# lednode.net
KiCad netlist of a schematic drawn in EAGLE
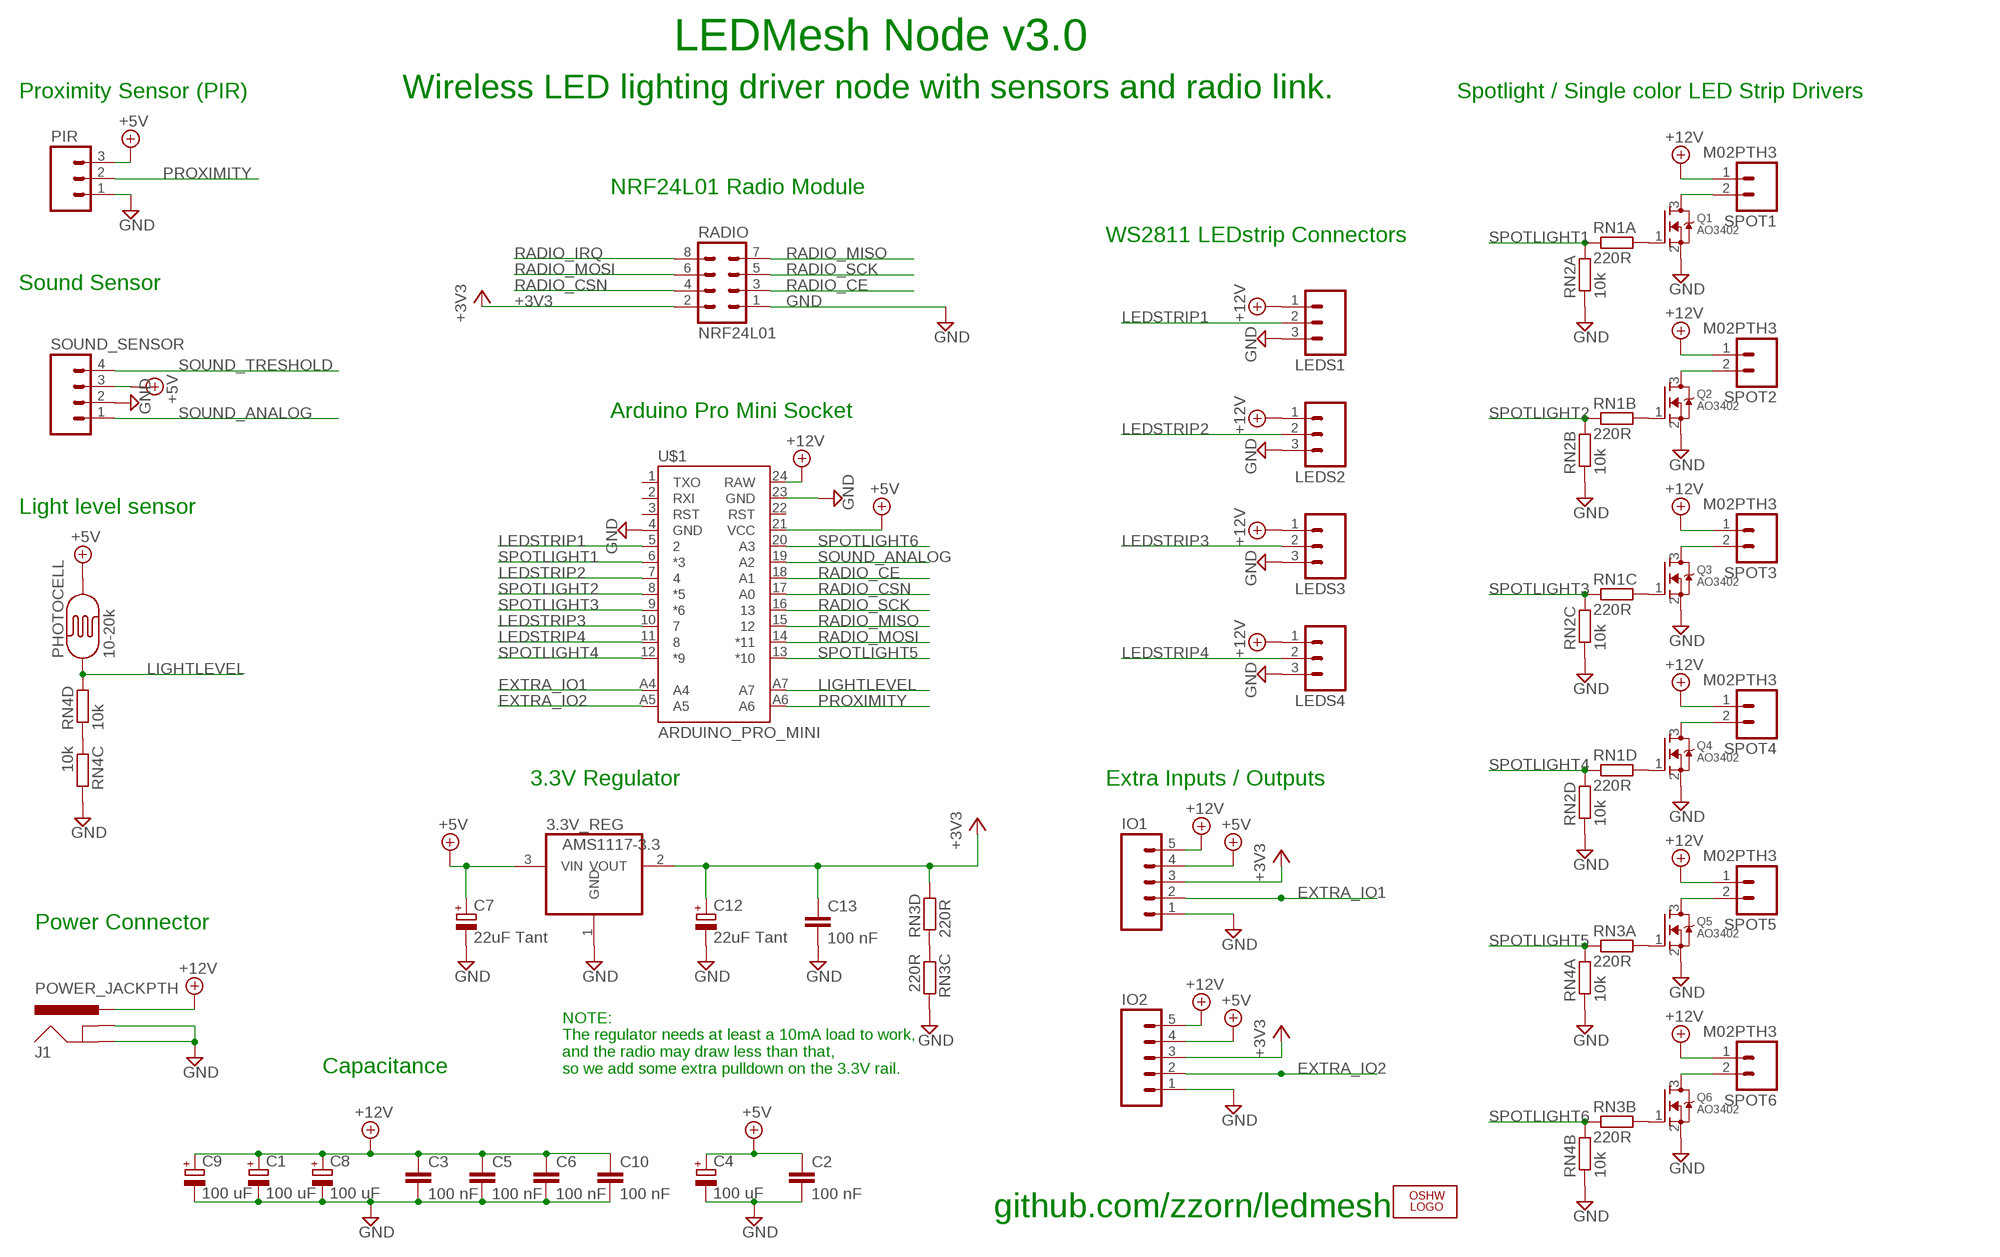
[diagram p0: schematic, sheet 1]

(export (version "E")
  (design (tool "Eeschema 10.0.6"))
  (components
    (comp (ref "3.3V_REG")
      (value "AMS1117-3.3")
      (footprint "eagle-import:SOT223")
      (fields (field (name "MPN") "REG1117"))
      (libsource (lib "eagle-import") (part "REG1117"))
    )
    (comp (ref "C1")
      (value "100 uF")
      (footprint "eagle-import:E2,5-6")
      (libsource (lib "eagle-import") (part "CPOL-EUE2.5-6"))
    )
    (comp (ref "C2")
      (value "100 nF")
      (footprint "eagle-import:C0805")
      (libsource (lib "eagle-import") (part "C-EUC0805"))
    )
    (comp (ref "C3")
      (value "100 nF")
      (footprint "eagle-import:C0805")
      (libsource (lib "eagle-import") (part "C-EUC0805"))
    )
    (comp (ref "C4")
      (value "100 uF")
      (footprint "eagle-import:E2,5-6")
      (libsource (lib "eagle-import") (part "CPOL-EUE2.5-6"))
    )
    (comp (ref "C5")
      (value "100 nF")
      (footprint "eagle-import:C0805")
      (libsource (lib "eagle-import") (part "C-EUC0805"))
    )
    (comp (ref "C6")
      (value "100 nF")
      (footprint "eagle-import:C0805")
      (libsource (lib "eagle-import") (part "C-EUC0805"))
    )
    (comp (ref "C7")
      (value "22uF Tant")
      (footprint "eagle-import:SMC_A")
      (libsource (lib "eagle-import") (part "CPOL-EUSMCA"))
    )
    (comp (ref "C8")
      (value "100 uF")
      (footprint "eagle-import:E2,5-6")
      (libsource (lib "eagle-import") (part "CPOL-EUE2.5-6"))
    )
    (comp (ref "C9")
      (value "100 uF")
      (footprint "eagle-import:E2,5-6")
      (libsource (lib "eagle-import") (part "CPOL-EUE2.5-6"))
    )
    (comp (ref "C10")
      (value "100 nF")
      (footprint "eagle-import:C0805")
      (libsource (lib "eagle-import") (part "C-EUC0805"))
    )
    (comp (ref "C12")
      (value "22uF Tant")
      (footprint "eagle-import:SMC_A")
      (libsource (lib "eagle-import") (part "CPOL-EUSMCA"))
    )
    (comp (ref "C13")
      (value "100 nF")
      (footprint "eagle-import:C0805")
      (libsource (lib "eagle-import") (part "C-EUC0805"))
    )
    (comp (ref "IO1")
      (value "M05PTH")
      (footprint "eagle-import:1X05")
      (libsource (lib "eagle-import") (part "M05PTH"))
    )
    (comp (ref "IO2")
      (value "M05PTH")
      (footprint "eagle-import:1X05")
      (libsource (lib "eagle-import") (part "M05PTH"))
    )
    (comp (ref "J1")
      (value "POWER_JACKPTH")
      (footprint "eagle-import:POWER_JACK_PTH")
      (libsource (lib "eagle-import") (part "POWER_JACKPTH"))
    )
    (comp (ref "LEDS1")
      (value "M03LONGPADS")
      (footprint "eagle-import:1X03_LONGPADS")
      (libsource (lib "eagle-import") (part "M03LONGPADS"))
    )
    (comp (ref "LEDS2")
      (value "M03LONGPADS")
      (footprint "eagle-import:1X03_LONGPADS")
      (libsource (lib "eagle-import") (part "M03LONGPADS"))
    )
    (comp (ref "LEDS3")
      (value "M03LONGPADS")
      (footprint "eagle-import:1X03_LONGPADS")
      (libsource (lib "eagle-import") (part "M03LONGPADS"))
    )
    (comp (ref "LEDS4")
      (value "M03LONGPADS")
      (footprint "eagle-import:1X03_LONGPADS")
      (libsource (lib "eagle-import") (part "M03LONGPADS"))
    )
    (comp (ref "LOGO3")
      (value "LOGO-OSHW-8MILX0100-NT")
      (footprint "eagle-import:OSHW_8X100_NOTEXT")
      (libsource (lib "eagle-import") (part "LOGO-OSHW-8MILX0100-NT"))
    )
    (comp (ref "PHOTOCELL")
      (value "10-20k")
      (footprint "eagle-import:PHOTOCELL")
      (libsource (lib "eagle-import") (part "PHOTOCELLPTH"))
    )
    (comp (ref "PIR")
      (value "M03PTH")
      (footprint "eagle-import:1X03")
      (libsource (lib "eagle-import") (part "M03PTH"))
    )
    (comp (ref "Q1")
      (value "AO3402")
      (footprint "eagle-import:SOT23-W")
      (libsource (lib "eagle-import") (part "MOSFET-NWAVE"))
    )
    (comp (ref "Q2")
      (value "AO3402")
      (footprint "eagle-import:SOT23-W")
      (libsource (lib "eagle-import") (part "MOSFET-NWAVE"))
    )
    (comp (ref "Q3")
      (value "AO3402")
      (footprint "eagle-import:SOT23-W")
      (libsource (lib "eagle-import") (part "MOSFET-NWAVE"))
    )
    (comp (ref "Q4")
      (value "AO3402")
      (footprint "eagle-import:SOT23-W")
      (libsource (lib "eagle-import") (part "MOSFET-NWAVE"))
    )
    (comp (ref "Q5")
      (value "AO3402")
      (footprint "eagle-import:SOT23-W")
      (libsource (lib "eagle-import") (part "MOSFET-NWAVE"))
    )
    (comp (ref "Q6")
      (value "AO3402")
      (footprint "eagle-import:SOT23-W")
      (libsource (lib "eagle-import") (part "MOSFET-NWAVE"))
    )
    (comp (ref "RADIO")
      (value "NRF24L01")
      (footprint "eagle-import:MA04-2")
      (libsource (lib "eagle-import") (part "MA04-2"))
    )
    (comp (ref "RN1")
      (value "220R")
      (footprint "eagle-import:RN8P-4R-CRA06S")
      (libsource (lib "eagle-import") (part "RESISTOR_ARRAY_4"))
    )
    (comp (ref "RN2")
      (value "10k")
      (footprint "eagle-import:RN8P-4R-CRA06S")
      (libsource (lib "eagle-import") (part "RESISTOR_ARRAY_4"))
    )
    (comp (ref "RN3")
      (value "220R")
      (footprint "eagle-import:RN8P-4R-CRA06S")
      (libsource (lib "eagle-import") (part "RESISTOR_ARRAY_4"))
    )
    (comp (ref "RN4")
      (value "10k")
      (footprint "eagle-import:RN8P-4R-CRA06S")
      (libsource (lib "eagle-import") (part "RESISTOR_ARRAY_4"))
    )
    (comp (ref "SOUND_SENSOR")
      (value "M041X04_NO_SILK")
      (footprint "eagle-import:1X04_NO_SILK")
      (libsource (lib "eagle-import") (part "M041X04_NO_SILK"))
    )
    (comp (ref "SPOT1")
      (value "M02PTH3")
      (footprint "eagle-import:1X02_LONGPADS")
      (libsource (lib "eagle-import") (part "M02PTH3"))
    )
    (comp (ref "SPOT2")
      (value "M02PTH3")
      (footprint "eagle-import:1X02_LONGPADS")
      (libsource (lib "eagle-import") (part "M02PTH3"))
    )
    (comp (ref "SPOT3")
      (value "M02PTH3")
      (footprint "eagle-import:1X02_LONGPADS")
      (libsource (lib "eagle-import") (part "M02PTH3"))
    )
    (comp (ref "SPOT4")
      (value "M02PTH3")
      (footprint "eagle-import:1X02_LONGPADS")
      (libsource (lib "eagle-import") (part "M02PTH3"))
    )
    (comp (ref "SPOT5")
      (value "M02PTH3")
      (footprint "eagle-import:1X02_LONGPADS")
      (libsource (lib "eagle-import") (part "M02PTH3"))
    )
    (comp (ref "SPOT6")
      (value "M02PTH3")
      (footprint "eagle-import:1X02_LONGPADS")
      (libsource (lib "eagle-import") (part "M02PTH3"))
    )
    (comp (ref "U$1")
      (value "ARDUINO_PRO_MINI")
      (footprint "eagle-import:ARDUINO_PRO_MINI")
      (libsource (lib "eagle-import") (part "ARDUINO_PRO_MINI"))
    )
  )
  (nets
    (net (code "1") (name "+3V3") (class "Default")
      (node (ref "3.3V_REG") (pin "2") (pinfunction "VOUT_2") (pintype "output"))
      (node (ref "C12") (pin "+") (pinfunction "+_+") (pintype "passive"))
      (node (ref "C13") (pin "1") (pinfunction "1_1") (pintype "passive"))
      (node (ref "IO1") (pin "3") (pinfunction "3_3") (pintype "passive"))
      (node (ref "IO2") (pin "3") (pinfunction "3_3") (pintype "passive"))
      (node (ref "RADIO") (pin "2") (pinfunction "2_2") (pintype "passive"))
      (node (ref "RN3") (pin "5") (pinfunction "2_5") (pintype "passive"))
    )
    (net (code "2") (name "+5V") (class "Default")
      (node (ref "3.3V_REG") (pin "3") (pinfunction "VIN_3") (pintype "input"))
      (node (ref "C2") (pin "1") (pinfunction "1_1") (pintype "passive"))
      (node (ref "C4") (pin "+") (pinfunction "+_+") (pintype "passive"))
      (node (ref "C7") (pin "+") (pinfunction "+_+") (pintype "passive"))
      (node (ref "IO1") (pin "4") (pinfunction "4_4") (pintype "passive"))
      (node (ref "IO2") (pin "4") (pinfunction "4_4") (pintype "passive"))
      (node (ref "PHOTOCELL") (pin "2") (pinfunction "P$2_2") (pintype "bidirectional"))
      (node (ref "PIR") (pin "3") (pinfunction "3_3") (pintype "passive"))
      (node (ref "SOUND_SENSOR") (pin "3") (pinfunction "3_3") (pintype "passive"))
      (node (ref "U$1") (pin "21") (pinfunction "VCC_21") (pintype "bidirectional"))
    )
    (net (code "3") (name "+12V") (class "Default")
      (node (ref "C1") (pin "+") (pinfunction "+_+") (pintype "passive"))
      (node (ref "C10") (pin "1") (pinfunction "1_1") (pintype "passive"))
      (node (ref "C3") (pin "1") (pinfunction "1_1") (pintype "passive"))
      (node (ref "C5") (pin "1") (pinfunction "1_1") (pintype "passive"))
      (node (ref "C6") (pin "1") (pinfunction "1_1") (pintype "passive"))
      (node (ref "C8") (pin "+") (pinfunction "+_+") (pintype "passive"))
      (node (ref "C9") (pin "+") (pinfunction "+_+") (pintype "passive"))
      (node (ref "IO1") (pin "5") (pinfunction "5_5") (pintype "passive"))
      (node (ref "IO2") (pin "5") (pinfunction "5_5") (pintype "passive"))
      (node (ref "J1") (pin "PWR") (pinfunction "PWR_PWR") (pintype "bidirectional"))
      (node (ref "LEDS1") (pin "1") (pinfunction "1_1") (pintype "passive"))
      (node (ref "LEDS2") (pin "1") (pinfunction "1_1") (pintype "passive"))
      (node (ref "LEDS3") (pin "1") (pinfunction "1_1") (pintype "passive"))
      (node (ref "LEDS4") (pin "1") (pinfunction "1_1") (pintype "passive"))
      (node (ref "SPOT1") (pin "1") (pinfunction "1_1") (pintype "passive"))
      (node (ref "SPOT2") (pin "1") (pinfunction "1_1") (pintype "passive"))
      (node (ref "SPOT3") (pin "1") (pinfunction "1_1") (pintype "passive"))
      (node (ref "SPOT4") (pin "1") (pinfunction "1_1") (pintype "passive"))
      (node (ref "SPOT5") (pin "1") (pinfunction "1_1") (pintype "passive"))
      (node (ref "SPOT6") (pin "1") (pinfunction "1_1") (pintype "passive"))
      (node (ref "U$1") (pin "24") (pinfunction "RAW_24") (pintype "bidirectional"))
    )
    (net (code "4") (name "/EXTRA_IO1") (class "Default")
      (node (ref "IO1") (pin "2") (pinfunction "2_2") (pintype "passive"))
      (node (ref "U$1") (pin "A4") (pinfunction "A4_A4") (pintype "bidirectional"))
    )
    (net (code "5") (name "/EXTRA_IO2") (class "Default")
      (node (ref "IO2") (pin "2") (pinfunction "2_2") (pintype "passive"))
      (node (ref "U$1") (pin "A5") (pinfunction "A5_A5") (pintype "bidirectional"))
    )
    (net (code "6") (name "/LEDSTRIP1") (class "Default")
      (node (ref "LEDS1") (pin "2") (pinfunction "2_2") (pintype "passive"))
      (node (ref "U$1") (pin "5") (pinfunction "2_5") (pintype "bidirectional"))
    )
    (net (code "7") (name "/LEDSTRIP2") (class "Default")
      (node (ref "LEDS2") (pin "2") (pinfunction "2_2") (pintype "passive"))
      (node (ref "U$1") (pin "7") (pinfunction "4_7") (pintype "bidirectional"))
    )
    (net (code "8") (name "/LEDSTRIP3") (class "Default")
      (node (ref "LEDS3") (pin "2") (pinfunction "2_2") (pintype "passive"))
      (node (ref "U$1") (pin "10") (pinfunction "7_10") (pintype "bidirectional"))
    )
    (net (code "9") (name "/LEDSTRIP4") (class "Default")
      (node (ref "LEDS4") (pin "2") (pinfunction "2_2") (pintype "passive"))
      (node (ref "U$1") (pin "11") (pinfunction "8_11") (pintype "bidirectional"))
    )
    (net (code "10") (name "/LIGHTLEVEL") (class "Default")
      (node (ref "PHOTOCELL") (pin "1") (pinfunction "P$1_1") (pintype "bidirectional"))
      (node (ref "RN4") (pin "5") (pinfunction "2_5") (pintype "passive"))
      (node (ref "U$1") (pin "A7") (pinfunction "A7_A7") (pintype "bidirectional"))
    )
    (net (code "11") (name "/PROXIMITY") (class "Default")
      (node (ref "PIR") (pin "2") (pinfunction "2_2") (pintype "passive"))
      (node (ref "U$1") (pin "A6") (pinfunction "A6_A6") (pintype "bidirectional"))
    )
    (net (code "12") (name "/RADIO_CE") (class "Default")
      (node (ref "RADIO") (pin "3") (pinfunction "3_3") (pintype "passive"))
      (node (ref "U$1") (pin "18") (pinfunction "A1_18") (pintype "bidirectional"))
    )
    (net (code "13") (name "/RADIO_CSN") (class "Default")
      (node (ref "RADIO") (pin "4") (pinfunction "4_4") (pintype "passive"))
      (node (ref "U$1") (pin "17") (pinfunction "A0_17") (pintype "bidirectional"))
    )
    (net (code "14") (name "/RADIO_IRQ") (class "Default")
      (node (ref "RADIO") (pin "8") (pinfunction "8_8") (pintype "passive"))
    )
    (net (code "15") (name "/RADIO_MISO") (class "Default")
      (node (ref "RADIO") (pin "7") (pinfunction "7_7") (pintype "passive"))
      (node (ref "U$1") (pin "15") (pinfunction "12_15") (pintype "bidirectional"))
    )
    (net (code "16") (name "/RADIO_MOSI") (class "Default")
      (node (ref "RADIO") (pin "6") (pinfunction "6_6") (pintype "passive"))
      (node (ref "U$1") (pin "14") (pinfunction "*11_14") (pintype "bidirectional"))
    )
    (net (code "17") (name "/RADIO_SCK") (class "Default")
      (node (ref "RADIO") (pin "5") (pinfunction "5_5") (pintype "passive"))
      (node (ref "U$1") (pin "16") (pinfunction "13_16") (pintype "bidirectional"))
    )
    (net (code "18") (name "/SOUND_ANALOG") (class "Default")
      (node (ref "SOUND_SENSOR") (pin "1") (pinfunction "1_1") (pintype "passive"))
      (node (ref "U$1") (pin "19") (pinfunction "A2_19") (pintype "bidirectional"))
    )
    (net (code "19") (name "/SOUND_TRESHOLD") (class "Default")
      (node (ref "SOUND_SENSOR") (pin "4") (pinfunction "4_4") (pintype "passive"))
    )
    (net (code "20") (name "/SPOTLIGHT1") (class "Default")
      (node (ref "RN1") (pin "1") (pinfunction "1_1") (pintype "passive"))
      (node (ref "RN2") (pin "8") (pinfunction "2_8") (pintype "passive"))
      (node (ref "U$1") (pin "6") (pinfunction "*3_6") (pintype "bidirectional"))
    )
    (net (code "21") (name "/SPOTLIGHT2") (class "Default")
      (node (ref "RN1") (pin "2") (pinfunction "1_2") (pintype "passive"))
      (node (ref "RN2") (pin "7") (pinfunction "2_7") (pintype "passive"))
      (node (ref "U$1") (pin "8") (pinfunction "*5_8") (pintype "bidirectional"))
    )
    (net (code "22") (name "/SPOTLIGHT3") (class "Default")
      (node (ref "RN1") (pin "3") (pinfunction "1_3") (pintype "passive"))
      (node (ref "RN2") (pin "6") (pinfunction "2_6") (pintype "passive"))
      (node (ref "U$1") (pin "9") (pinfunction "*6_9") (pintype "bidirectional"))
    )
    (net (code "23") (name "/SPOTLIGHT4") (class "Default")
      (node (ref "RN1") (pin "4") (pinfunction "1_4") (pintype "passive"))
      (node (ref "RN2") (pin "5") (pinfunction "2_5") (pintype "passive"))
      (node (ref "U$1") (pin "12") (pinfunction "*9_12") (pintype "bidirectional"))
    )
    (net (code "24") (name "/SPOTLIGHT5") (class "Default")
      (node (ref "RN3") (pin "1") (pinfunction "1_1") (pintype "passive"))
      (node (ref "RN4") (pin "8") (pinfunction "2_8") (pintype "passive"))
      (node (ref "U$1") (pin "13") (pinfunction "*10_13") (pintype "bidirectional"))
    )
    (net (code "25") (name "/SPOTLIGHT6") (class "Default")
      (node (ref "RN3") (pin "2") (pinfunction "1_2") (pintype "passive"))
      (node (ref "RN4") (pin "7") (pinfunction "2_7") (pintype "passive"))
      (node (ref "U$1") (pin "20") (pinfunction "A3_20") (pintype "bidirectional"))
    )
    (net (code "26") (name "GND") (class "Default")
      (node (ref "3.3V_REG") (pin "1") (pinfunction "GND_1") (pintype "power_in"))
      (node (ref "C1") (pin "-") (pinfunction "-_-") (pintype "passive"))
      (node (ref "C10") (pin "2") (pinfunction "2_2") (pintype "passive"))
      (node (ref "C12") (pin "-") (pinfunction "-_-") (pintype "passive"))
      (node (ref "C13") (pin "2") (pinfunction "2_2") (pintype "passive"))
      (node (ref "C2") (pin "2") (pinfunction "2_2") (pintype "passive"))
      (node (ref "C3") (pin "2") (pinfunction "2_2") (pintype "passive"))
      (node (ref "C4") (pin "-") (pinfunction "-_-") (pintype "passive"))
      (node (ref "C5") (pin "2") (pinfunction "2_2") (pintype "passive"))
      (node (ref "C6") (pin "2") (pinfunction "2_2") (pintype "passive"))
      (node (ref "C7") (pin "-") (pinfunction "-_-") (pintype "passive"))
      (node (ref "C8") (pin "-") (pinfunction "-_-") (pintype "passive"))
      (node (ref "C9") (pin "-") (pinfunction "-_-") (pintype "passive"))
      (node (ref "IO1") (pin "1") (pinfunction "1_1") (pintype "passive"))
      (node (ref "IO2") (pin "1") (pinfunction "1_1") (pintype "passive"))
      (node (ref "J1") (pin "GND") (pinfunction "GND_GND") (pintype "bidirectional"))
      (node (ref "J1") (pin "GNDBREAK") (pinfunction "GNDBREAK_GNDBREAK") (pintype "bidirectional"))
      (node (ref "LEDS1") (pin "3") (pinfunction "3_3") (pintype "passive"))
      (node (ref "LEDS2") (pin "3") (pinfunction "3_3") (pintype "passive"))
      (node (ref "LEDS3") (pin "3") (pinfunction "3_3") (pintype "passive"))
      (node (ref "LEDS4") (pin "3") (pinfunction "3_3") (pintype "passive"))
      (node (ref "PIR") (pin "1") (pinfunction "1_1") (pintype "passive"))
      (node (ref "Q1") (pin "2") (pinfunction "S_2") (pintype "bidirectional"))
      (node (ref "Q2") (pin "2") (pinfunction "S_2") (pintype "bidirectional"))
      (node (ref "Q3") (pin "2") (pinfunction "S_2") (pintype "bidirectional"))
      (node (ref "Q4") (pin "2") (pinfunction "S_2") (pintype "bidirectional"))
      (node (ref "Q5") (pin "2") (pinfunction "S_2") (pintype "bidirectional"))
      (node (ref "Q6") (pin "2") (pinfunction "S_2") (pintype "bidirectional"))
      (node (ref "RADIO") (pin "1") (pinfunction "1_1") (pintype "passive"))
      (node (ref "RN2") (pin "1") (pinfunction "1_1") (pintype "passive"))
      (node (ref "RN2") (pin "2") (pinfunction "1_2") (pintype "passive"))
      (node (ref "RN2") (pin "3") (pinfunction "1_3") (pintype "passive"))
      (node (ref "RN2") (pin "4") (pinfunction "1_4") (pintype "passive"))
      (node (ref "RN3") (pin "6") (pinfunction "2_6") (pintype "passive"))
      (node (ref "RN4") (pin "1") (pinfunction "1_1") (pintype "passive"))
      (node (ref "RN4") (pin "2") (pinfunction "1_2") (pintype "passive"))
      (node (ref "RN4") (pin "6") (pinfunction "2_6") (pintype "passive"))
      (node (ref "SOUND_SENSOR") (pin "2") (pinfunction "2_2") (pintype "passive"))
      (node (ref "U$1") (pin "23") (pinfunction "GND_23") (pintype "bidirectional"))
      (node (ref "U$1") (pin "4") (pinfunction "GND_4") (pintype "bidirectional"))
    )
    (net (code "27") (name "Net-(Q1-D)") (class "Default")
      (node (ref "Q1") (pin "3") (pinfunction "D_3") (pintype "bidirectional"))
      (node (ref "SPOT1") (pin "2") (pinfunction "2_2") (pintype "passive"))
    )
    (net (code "28") (name "Net-(Q1-G)") (class "Default")
      (node (ref "Q1") (pin "1") (pinfunction "G_1") (pintype "bidirectional"))
      (node (ref "RN1") (pin "8") (pinfunction "2_8") (pintype "passive"))
    )
    (net (code "29") (name "Net-(Q2-D)") (class "Default")
      (node (ref "Q2") (pin "3") (pinfunction "D_3") (pintype "bidirectional"))
      (node (ref "SPOT2") (pin "2") (pinfunction "2_2") (pintype "passive"))
    )
    (net (code "30") (name "Net-(Q2-G)") (class "Default")
      (node (ref "Q2") (pin "1") (pinfunction "G_1") (pintype "bidirectional"))
      (node (ref "RN1") (pin "7") (pinfunction "2_7") (pintype "passive"))
    )
    (net (code "31") (name "Net-(Q3-D)") (class "Default")
      (node (ref "Q3") (pin "3") (pinfunction "D_3") (pintype "bidirectional"))
      (node (ref "SPOT3") (pin "2") (pinfunction "2_2") (pintype "passive"))
    )
    (net (code "32") (name "Net-(Q3-G)") (class "Default")
      (node (ref "Q3") (pin "1") (pinfunction "G_1") (pintype "bidirectional"))
      (node (ref "RN1") (pin "6") (pinfunction "2_6") (pintype "passive"))
    )
    (net (code "33") (name "Net-(Q4-D)") (class "Default")
      (node (ref "Q4") (pin "3") (pinfunction "D_3") (pintype "bidirectional"))
      (node (ref "SPOT4") (pin "2") (pinfunction "2_2") (pintype "passive"))
    )
    (net (code "34") (name "Net-(Q4-G)") (class "Default")
      (node (ref "Q4") (pin "1") (pinfunction "G_1") (pintype "bidirectional"))
      (node (ref "RN1") (pin "5") (pinfunction "2_5") (pintype "passive"))
    )
    (net (code "35") (name "Net-(Q5-D)") (class "Default")
      (node (ref "Q5") (pin "3") (pinfunction "D_3") (pintype "bidirectional"))
      (node (ref "SPOT5") (pin "2") (pinfunction "2_2") (pintype "passive"))
    )
    (net (code "36") (name "Net-(Q5-G)") (class "Default")
      (node (ref "Q5") (pin "1") (pinfunction "G_1") (pintype "bidirectional"))
      (node (ref "RN3") (pin "8") (pinfunction "2_8") (pintype "passive"))
    )
    (net (code "37") (name "Net-(Q6-D)") (class "Default")
      (node (ref "Q6") (pin "3") (pinfunction "D_3") (pintype "bidirectional"))
      (node (ref "SPOT6") (pin "2") (pinfunction "2_2") (pintype "passive"))
    )
    (net (code "38") (name "Net-(Q6-G)") (class "Default")
      (node (ref "Q6") (pin "1") (pinfunction "G_1") (pintype "bidirectional"))
      (node (ref "RN3") (pin "7") (pinfunction "2_7") (pintype "passive"))
    )
    (net (code "39") (name "Net-(RN3C-1)") (class "Default")
      (node (ref "RN3") (pin "3") (pinfunction "1_3") (pintype "passive"))
      (node (ref "RN3") (pin "4") (pinfunction "1_4") (pintype "passive"))
    )
    (net (code "40") (name "Net-(RN4C-1)") (class "Default")
      (node (ref "RN4") (pin "3") (pinfunction "1_3") (pintype "passive"))
      (node (ref "RN4") (pin "4") (pinfunction "1_4") (pintype "passive"))
    )
    (net (code "41") (name "unconnected-(U$1-RST-Pad3)") (class "Default")
      (node (ref "U$1") (pin "3") (pinfunction "RST_3") (pintype "bidirectional"))
    )
    (net (code "42") (name "unconnected-(U$1-RST-Pad22)") (class "Default")
      (node (ref "U$1") (pin "22") (pinfunction "RST_22") (pintype "bidirectional"))
    )
    (net (code "43") (name "unconnected-(U$1-RXI-Pad2)") (class "Default")
      (node (ref "U$1") (pin "2") (pinfunction "RXI_2") (pintype "bidirectional"))
    )
    (net (code "44") (name "unconnected-(U$1-TXO-Pad1)") (class "Default")
      (node (ref "U$1") (pin "1") (pinfunction "TXO_1") (pintype "bidirectional"))
    )
  )
)
